# Sheet1.net
KiCad netlist of a schematic drawn in Altium Designer
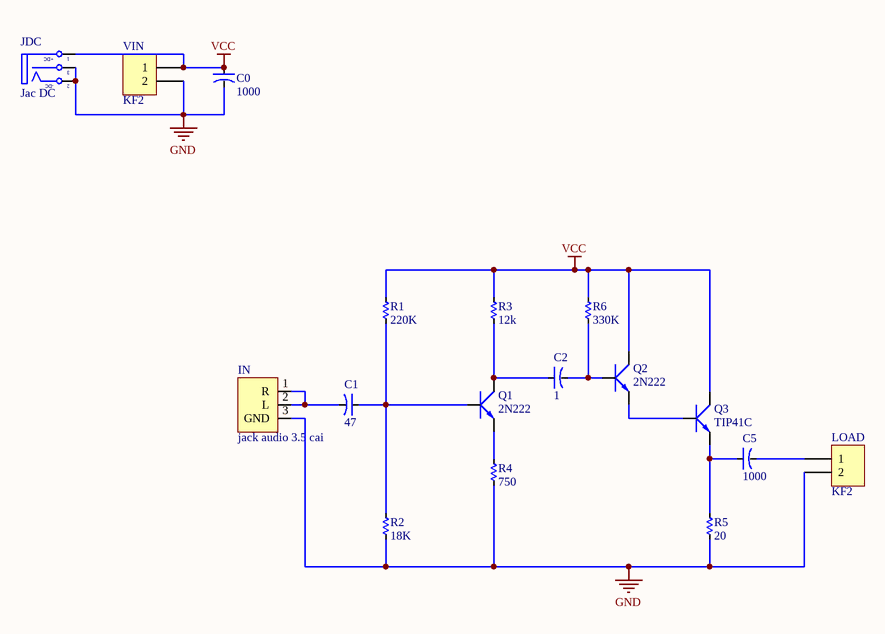
[diagram p0: Sheet1.SchDoc]

(export (version "E")
  (design (tool "Eeschema 10.0.6"))
  (components
    (comp (ref "C0")
      (value "1000")
      (footprint "CA-ALU-8")
      (description "Capacitor (Semiconductor SIM Model)")
      (fields (field (name "PUBLISHER") "Altium Limited"))
      (libsource (lib "LIBRARY") (part "CN-ALU-DIP"))
    )
    (comp (ref "C1")
      (value "47")
      (footprint "CA-ALU-6.3")
      (description "Capacitor (Semiconductor SIM Model)")
      (fields (field (name "PUBLISHER") "Altium Limited"))
      (libsource (lib "LIBRARY") (part "CN-ALU-DIP"))
    )
    (comp (ref "C2")
      (value "1")
      (footprint "CA-ALU-6.3")
      (description "Capacitor (Semiconductor SIM Model)")
      (fields (field (name "PUBLISHER") "Altium Limited"))
      (libsource (lib "LIBRARY") (part "CN-ALU-DIP"))
    )
    (comp (ref "C5")
      (value "1000")
      (footprint "CA-ALU-13BL")
      (description "Capacitor (Semiconductor SIM Model)")
      (fields (field (name "PUBLISHER") "Altium Limited"))
      (libsource (lib "LIBRARY") (part "CN-ALU-DIP"))
    )
    (comp (ref "IN")
      (value "jack audio 3.5 cai")
      (footprint "Jack audio 3.5 PJ-313")
      (libsource (lib "TrongCz") (part "jack audio 3.5 cai"))
    )
    (comp (ref "JDC")
      (value "Jac DC")
      (footprint "DC5")
      (description "Jac DC input")
      (libsource (lib "LIBRARY") (part "DCIN"))
    )
    (comp (ref "LOAD")
      (value "KF2")
      (footprint "KF2-5.08")
      (fields
        (field (name "MANUFACTURER") "Würth Elektronik eiSos GmbH")
        (field (name "PARTNO") "691103110002")
        (field (name "CREATED BY") "Karrer Zheng")
      )
      (libsource (lib "LIBRARY") (part "KF2"))
    )
    (comp (ref "Q1")
      (value "2N222")
      (footprint "TO92-123")
      (description "NPN 600mW, ECB")
      (libsource (lib "LIBRARY") (part "2N222"))
    )
    (comp (ref "Q2")
      (value "2N222")
      (footprint "TO92-123")
      (description "NPN 600mW, ECB")
      (libsource (lib "LIBRARY") (part "2N222"))
    )
    (comp (ref "Q3")
      (value "TIP41C")
      (footprint "TO220-123")
      (description "NPN 2W, BCE")
      (libsource (lib "LIBRARY") (part "TIP41C"))
    )
    (comp (ref "R1")
      (value "220K")
      (footprint "RES-1/4W")
      (description "Res")
      (fields
        (field (name "MANUFACTURER") "Generic Components")
        (field (name "PUBLISHER") "Altium Hobart Technology Centre")
      )
      (libsource (lib "LIBRARY") (part "Res"))
    )
    (comp (ref "R2")
      (value "18K")
      (footprint "RES-1/4W")
      (description "Res")
      (fields
        (field (name "MANUFACTURER") "Generic Components")
        (field (name "PUBLISHER") "Altium Hobart Technology Centre")
      )
      (libsource (lib "LIBRARY") (part "Res"))
    )
    (comp (ref "R3")
      (value "12k")
      (footprint "RES-1/4W")
      (description "Res")
      (fields
        (field (name "MANUFACTURER") "Generic Components")
        (field (name "PUBLISHER") "Altium Hobart Technology Centre")
      )
      (libsource (lib "LIBRARY") (part "Res"))
    )
    (comp (ref "R4")
      (value "750")
      (footprint "RES-1/4W")
      (description "Res")
      (fields
        (field (name "MANUFACTURER") "Generic Components")
        (field (name "PUBLISHER") "Altium Hobart Technology Centre")
      )
      (libsource (lib "LIBRARY") (part "Res"))
    )
    (comp (ref "R5")
      (value "20")
      (footprint "RES-5W")
      (description "Res")
      (fields
        (field (name "MANUFACTURER") "Generic Components")
        (field (name "PUBLISHER") "Altium Hobart Technology Centre")
      )
      (libsource (lib "LIBRARY") (part "Res"))
    )
    (comp (ref "R6")
      (value "330K")
      (footprint "RES-1/4W")
      (description "Res")
      (fields
        (field (name "MANUFACTURER") "Generic Components")
        (field (name "PUBLISHER") "Altium Hobart Technology Centre")
      )
      (libsource (lib "LIBRARY") (part "Res"))
    )
    (comp (ref "VIN")
      (value "KF2")
      (footprint "KF2-5.08")
      (fields
        (field (name "MANUFACTURER") "Würth Elektronik eiSos GmbH")
        (field (name "PARTNO") "691103110002")
        (field (name "CREATED BY") "Karrer Zheng")
      )
      (libsource (lib "") (part "KF2_1"))
    )
  )
  (nets
    (net (code "1") (name "GND") (class "Default")
      (node (ref "C0") (pin "2") (pinfunction "2_2") (pintype "passive"))
      (node (ref "IN") (pin "3") (pinfunction "GND_3") (pintype "passive"))
      (node (ref "JDC") (pin "2") (pinfunction "TN_2") (pintype "passive"))
      (node (ref "JDC") (pin "3") (pinfunction "S_3") (pintype "power_in"))
      (node (ref "LOAD") (pin "2") (pinfunction "2_2") (pintype "passive"))
      (node (ref "R2") (pin "2") (pinfunction "2_2") (pintype "passive"))
      (node (ref "R4") (pin "2") (pinfunction "2_2") (pintype "passive"))
      (node (ref "R5") (pin "2") (pinfunction "2_2") (pintype "passive"))
      (node (ref "VIN") (pin "2") (pinfunction "2_2") (pintype "passive"))
    )
    (net (code "2") (name "Net-(C5-Pad2)") (class "Default")
      (node (ref "C5") (pin "2") (pinfunction "2_2") (pintype "passive"))
      (node (ref "LOAD") (pin "1") (pinfunction "1_1") (pintype "passive"))
    )
    (net (code "3") (name "Net-(IN-L)") (class "Default")
      (node (ref "C1") (pin "2") (pinfunction "2_2") (pintype "passive"))
      (node (ref "IN") (pin "1") (pinfunction "R_1") (pintype "passive"))
      (node (ref "IN") (pin "2") (pinfunction "L_2") (pintype "passive"))
    )
    (net (code "4") (name "Net-(Q1-B)") (class "Default")
      (node (ref "C1") (pin "1") (pinfunction "1_1") (pintype "passive"))
      (node (ref "Q1") (pin "2") (pinfunction "B_2") (pintype "passive"))
      (node (ref "R1") (pin "2") (pinfunction "2_2") (pintype "passive"))
      (node (ref "R2") (pin "1") (pinfunction "1_1") (pintype "passive"))
    )
    (net (code "5") (name "Net-(Q1-C)") (class "Default")
      (node (ref "C2") (pin "1") (pinfunction "1_1") (pintype "passive"))
      (node (ref "Q1") (pin "3") (pinfunction "C_3") (pintype "passive"))
      (node (ref "R3") (pin "2") (pinfunction "2_2") (pintype "passive"))
    )
    (net (code "6") (name "Net-(Q1-E)") (class "Default")
      (node (ref "Q1") (pin "1") (pinfunction "E_1") (pintype "passive"))
      (node (ref "R4") (pin "1") (pinfunction "1_1") (pintype "passive"))
    )
    (net (code "7") (name "Net-(Q2-B)") (class "Default")
      (node (ref "C2") (pin "2") (pinfunction "2_2") (pintype "passive"))
      (node (ref "Q2") (pin "2") (pinfunction "B_2") (pintype "passive"))
      (node (ref "R6") (pin "2") (pinfunction "2_2") (pintype "passive"))
    )
    (net (code "8") (name "Net-(Q2-E)") (class "Default")
      (node (ref "Q2") (pin "1") (pinfunction "E_1") (pintype "passive"))
      (node (ref "Q3") (pin "1") (pinfunction "B_1") (pintype "passive"))
    )
    (net (code "9") (name "Net-(Q3-E)") (class "Default")
      (node (ref "C5") (pin "1") (pinfunction "1_1") (pintype "passive"))
      (node (ref "Q3") (pin "3") (pinfunction "E_3") (pintype "passive"))
      (node (ref "R5") (pin "1") (pinfunction "1_1") (pintype "passive"))
    )
    (net (code "10") (name "VCC") (class "Default")
      (node (ref "C0") (pin "1") (pinfunction "1_1") (pintype "passive"))
      (node (ref "JDC") (pin "1") (pinfunction "T_1") (pintype "passive"))
      (node (ref "Q2") (pin "3") (pinfunction "C_3") (pintype "passive"))
      (node (ref "Q3") (pin "2") (pinfunction "C_2") (pintype "passive"))
      (node (ref "R1") (pin "1") (pinfunction "1_1") (pintype "passive"))
      (node (ref "R3") (pin "1") (pinfunction "1_1") (pintype "passive"))
      (node (ref "R6") (pin "1") (pinfunction "1_1") (pintype "passive"))
      (node (ref "VIN") (pin "1") (pinfunction "1_1") (pintype "passive"))
    )
  )
)
